# PULSE_TRIGGER.net
KiCad netlist of a schematic drawn in Altium Designer
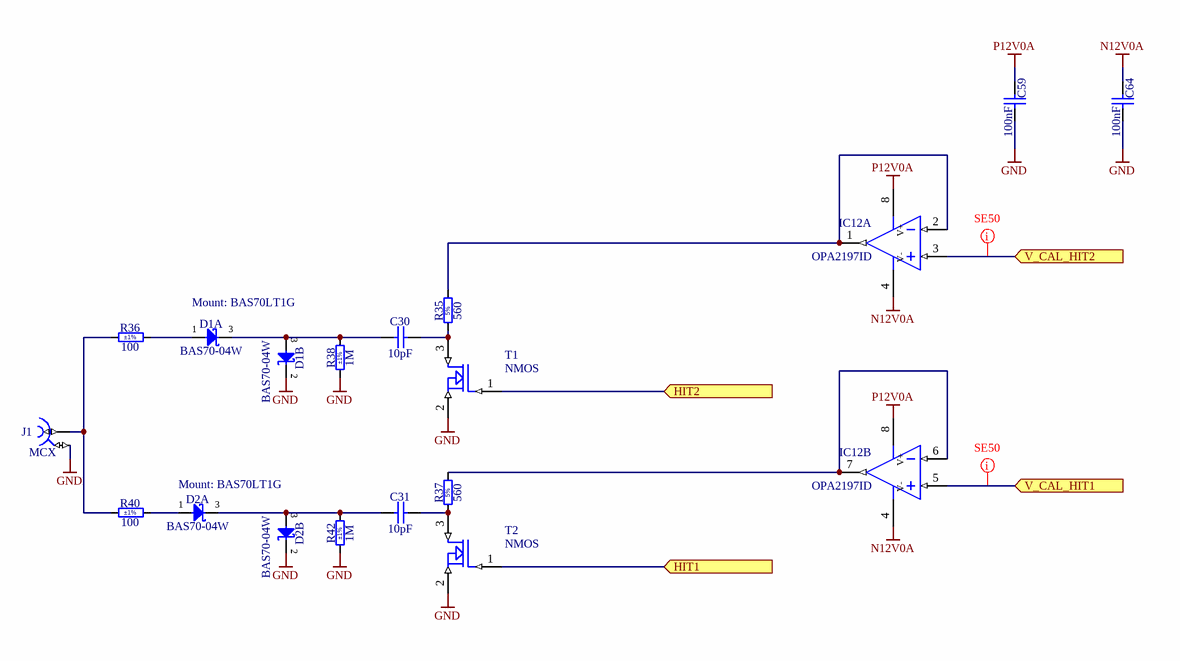
[diagram p0: PULSE_TRIGGER.SchDoc]

(export (version "E")
  (design (tool "Eeschema 10.0.6"))
  (components
    (comp (ref "C30")
      (value "10pF")
      (footprint "CAPC1608X87N")
      (description "Non-polarised capacitor")
      (fields
        (field (name "PART NUMBER") "CC0603_10PF_50V_5%_NP0")
        (field (name "VOLTAGE") "50V")
        (field (name "AUTHOR") "CERN DEM JLC")
      )
      (libsource (lib "Capacitors") (part "Capacitor - non polarized"))
    )
    (comp (ref "C31")
      (value "10pF")
      (footprint "CAPC1608X87N")
      (description "Non-polarised capacitor")
      (fields
        (field (name "PART NUMBER") "CC0603_10PF_50V_5%_NP0")
        (field (name "VOLTAGE") "50V")
        (field (name "AUTHOR") "CERN DEM JLC")
      )
      (libsource (lib "Capacitors") (part "Capacitor - non polarized"))
    )
    (comp (ref "C59")
      (value "100nF")
      (footprint "CAPC1005X55N")
      (description "Non-polarised capacitor")
      (fields
        (field (name "PART NUMBER") "CC0402_100NF_16V_10%_X7R")
        (field (name "VOLTAGE") "16V")
        (field (name "AUTHOR") "CERN DEM JLC")
      )
      (libsource (lib "Capacitors") (part "Capacitor - non polarized"))
    )
    (comp (ref "C64")
      (value "100nF")
      (footprint "CAPC1005X55N")
      (description "Non-polarised capacitor")
      (fields
        (field (name "PART NUMBER") "CC0402_100NF_16V_10%_X7R")
        (field (name "VOLTAGE") "16V")
        (field (name "AUTHOR") "CERN DEM JLC")
      )
      (libsource (lib "Capacitors") (part "Capacitor - non polarized"))
    )
    (comp (ref "D1")
      (value "BAS70-04W")
      (footprint "SOT65P210X110-3N")
      (description "Serial Schottky Diode")
      (fields
        (field (name "VOLTAGE") "70V")
        (field (name "POWER") "70mA")
        (field (name "AUTHOR") "CERN DEM JLC")
      )
      (libsource (lib "ICs And Semiconductors") (part "Diode Schottky x2 A1C3_A3C2"))
    )
    (comp (ref "D2")
      (value "BAS70-04W")
      (footprint "SOT65P210X110-3N")
      (description "Serial Schottky Diode")
      (fields
        (field (name "VOLTAGE") "70V")
        (field (name "POWER") "70mA")
        (field (name "AUTHOR") "CERN DEM JLC")
      )
      (libsource (lib "ICs And Semiconductors") (part "Diode Schottky x2 A1C3_A3C2"))
    )
    (comp (ref "IC12")
      (value "OPA2197ID")
      (footprint "SOIC127P600X175-8N")
      (description "Dual Operational Amplifier")
      (fields (field (name "MANUFACTURER") "TEXAS INSTRUMENTS") (field (name "AUTHOR") "CERN DEM MR"))
      (libsource (lib "ICs And Semiconductors") (part "Operational Amplifier x2 Type1"))
    )
    (comp (ref "J1")
      (value "MCX")
      (footprint "AMPHENOL_919-383J-51A")
      (fields
        (field (name "PART NUMBER") "AMPHENOL_919-383J-51A")
        (field (name "MANUFACTURER") "AMPHENOL")
        (field (name "MANUFACTURER PART NUMBER") "919-383J-51A")
        (field (name "AUTHOR") "CERN DEM BC")
      )
      (libsource (lib "Connectors") (part "Coax_1Female_1Shield"))
    )
    (comp (ref "R35")
      (value "560")
      (footprint "RESC2012X70N")
      (description "Resistor - 5%")
      (fields
        (field (name "PART NUMBER") "R0805_560R_5%_0.25W_200PPM_PANASONIC_ERJT")
        (field (name "POWER") "0.25W")
        (field (name "AUTHOR") "CERN DEM MR")
      )
      (libsource (lib "Resistors") (part "Resistor - 5%"))
    )
    (comp (ref "R36")
      (value "100")
      (footprint "RESC1608X55N")
      (description "Resistor - 1%")
      (fields
        (field (name "TOLERANCE") "±1%")
        (field (name "PART NUMBER") "R0603_100R_1%_0.1W_100PPM")
        (field (name "POWER") "0.1W")
        (field (name "AUTHOR") "CERN DEM JLC")
      )
      (libsource (lib "Resistors") (part "Resistor - 1%"))
    )
    (comp (ref "R37")
      (value "560")
      (footprint "RESC2012X70N")
      (description "Resistor - 5%")
      (fields
        (field (name "PART NUMBER") "R0805_560R_5%_0.25W_200PPM_PANASONIC_ERJT")
        (field (name "POWER") "0.25W")
        (field (name "AUTHOR") "CERN DEM MR")
      )
      (libsource (lib "Resistors") (part "Resistor - 5%"))
    )
    (comp (ref "R38")
      (value "1M")
      (footprint "RESC1608X55N")
      (description "Resistor - 1%")
      (fields
        (field (name "TOLERANCE") "±1%")
        (field (name "PART NUMBER") "R0603_1M_1%_0.1W_100PPM")
        (field (name "POWER") "0.1W")
        (field (name "AUTHOR") "CERN DEM JLC")
      )
      (libsource (lib "Resistors") (part "Resistor - 1%"))
    )
    (comp (ref "R40")
      (value "100")
      (footprint "RESC1608X55N")
      (description "Resistor - 1%")
      (fields
        (field (name "TOLERANCE") "±1%")
        (field (name "PART NUMBER") "R0603_100R_1%_0.1W_100PPM")
        (field (name "POWER") "0.1W")
        (field (name "AUTHOR") "CERN DEM JLC")
      )
      (libsource (lib "Resistors") (part "Resistor - 1%"))
    )
    (comp (ref "R42")
      (value "1M")
      (footprint "RESC1608X55N")
      (description "Resistor - 1%")
      (fields
        (field (name "TOLERANCE") "±1%")
        (field (name "PART NUMBER") "R0603_1M_1%_0.1W_100PPM")
        (field (name "POWER") "0.1W")
        (field (name "AUTHOR") "CERN DEM JLC")
      )
      (libsource (lib "Resistors") (part "Resistor - 1%"))
    )
    (comp (ref "T1")
      (value "NMOS")
      (footprint "CSD15380F3")
      (description "20-V, N channel NexFET™ power MOSFET, single LGA 0.6 mm x 0.7 mm, 1460 mOhm, gate ESD protection")
      (fields (field (name "MANUFACTURER PART NUMBER") "CSD15380F3"))
      (libsource (lib "LIBRARY_SCH") (part "Q_MOSFET N"))
    )
    (comp (ref "T2")
      (value "NMOS")
      (footprint "CSD15380F3")
      (description "20-V, N channel NexFET™ power MOSFET, single LGA 0.6 mm x 0.7 mm, 1460 mOhm, gate ESD protection")
      (fields (field (name "MANUFACTURER PART NUMBER") "CSD15380F3"))
      (libsource (lib "LIBRARY_SCH") (part "Q_MOSFET N"))
    )
  )
  (nets
    (net (code "1") (name "/HIT1") (class "Default")
      (node (ref "T2") (pin "1") (pinfunction "G_1") (pintype "input"))
    )
    (net (code "2") (name "/HIT2") (class "Default")
      (node (ref "T1") (pin "1") (pinfunction "G_1") (pintype "input"))
    )
    (net (code "3") (name "/V_CAL_HIT1") (class "Default")
      (node (ref "IC12") (pin "5") (pinfunction "IN+_5") (pintype "input"))
    )
    (net (code "4") (name "/V_CAL_HIT2") (class "Default")
      (node (ref "IC12") (pin "3") (pinfunction "IN+_3") (pintype "input"))
    )
    (net (code "5") (name "GND") (class "Default")
      (node (ref "C59") (pin "1") (pinfunction "1_1") (pintype "passive"))
      (node (ref "C64") (pin "1") (pinfunction "1_1") (pintype "passive"))
      (node (ref "D1") (pin "2") (pinfunction "C_2") (pintype "passive"))
      (node (ref "D2") (pin "2") (pinfunction "C_2") (pintype "passive"))
      (node (ref "J1") (pin "2") (pinfunction "2_2") (pintype "bidirectional"))
      (node (ref "R38") (pin "1") (pinfunction "1_1") (pintype "passive"))
      (node (ref "R42") (pin "1") (pinfunction "1_1") (pintype "passive"))
      (node (ref "T1") (pin "2") (pinfunction "S_2") (pintype "input"))
      (node (ref "T2") (pin "2") (pinfunction "S_2") (pintype "input"))
    )
    (net (code "6") (name "N12V0A") (class "Default")
      (node (ref "C64") (pin "2") (pinfunction "2_2") (pintype "passive"))
      (node (ref "IC12") (pin "4") (pinfunction "V-_4") (pintype "power_in"))
    )
    (net (code "7") (name "Net-(D1A-A)") (class "Default")
      (node (ref "D1") (pin "1") (pinfunction "A_1") (pintype "passive"))
      (node (ref "R36") (pin "2") (pinfunction "2_2") (pintype "passive"))
    )
    (net (code "8") (name "Net-(D1A-COMAC)") (class "Default")
      (node (ref "C30") (pin "1") (pinfunction "1_1") (pintype "passive"))
      (node (ref "D1") (pin "3") (pinfunction "COMAC_3") (pintype "passive"))
      (node (ref "R38") (pin "2") (pinfunction "2_2") (pintype "passive"))
    )
    (net (code "9") (name "Net-(D2A-A)") (class "Default")
      (node (ref "D2") (pin "1") (pinfunction "A_1") (pintype "passive"))
      (node (ref "R40") (pin "2") (pinfunction "2_2") (pintype "passive"))
    )
    (net (code "10") (name "Net-(D2A-COMAC)") (class "Default")
      (node (ref "C31") (pin "1") (pinfunction "1_1") (pintype "passive"))
      (node (ref "D2") (pin "3") (pinfunction "COMAC_3") (pintype "passive"))
      (node (ref "R42") (pin "2") (pinfunction "2_2") (pintype "passive"))
    )
    (net (code "11") (name "Net-(IC12A-IN-)") (class "Default")
      (node (ref "IC12") (pin "1") (pinfunction "OUT_1") (pintype "output"))
      (node (ref "IC12") (pin "2") (pinfunction "IN-_2") (pintype "input"))
      (node (ref "R35") (pin "2") (pinfunction "2_2") (pintype "passive"))
    )
    (net (code "12") (name "Net-(IC12B-IN-)") (class "Default")
      (node (ref "IC12") (pin "6") (pinfunction "IN-_6") (pintype "input"))
      (node (ref "IC12") (pin "7") (pinfunction "OUT_7") (pintype "output"))
      (node (ref "R37") (pin "2") (pinfunction "2_2") (pintype "passive"))
    )
    (net (code "13") (name "Net-(J1-Pad1)") (class "Default")
      (node (ref "J1") (pin "1") (pinfunction "1_1") (pintype "bidirectional"))
      (node (ref "R36") (pin "1") (pinfunction "1_1") (pintype "passive"))
      (node (ref "R40") (pin "1") (pinfunction "1_1") (pintype "passive"))
    )
    (net (code "14") (name "Net-(T1-D)") (class "Default")
      (node (ref "C30") (pin "2") (pinfunction "2_2") (pintype "passive"))
      (node (ref "R35") (pin "1") (pinfunction "1_1") (pintype "passive"))
      (node (ref "T1") (pin "3") (pinfunction "D_3") (pintype "input"))
    )
    (net (code "15") (name "Net-(T2-D)") (class "Default")
      (node (ref "C31") (pin "2") (pinfunction "2_2") (pintype "passive"))
      (node (ref "R37") (pin "1") (pinfunction "1_1") (pintype "passive"))
      (node (ref "T2") (pin "3") (pinfunction "D_3") (pintype "input"))
    )
    (net (code "16") (name "P12V0A") (class "Default")
      (node (ref "C59") (pin "2") (pinfunction "2_2") (pintype "passive"))
      (node (ref "IC12") (pin "8") (pinfunction "V+_8") (pintype "power_in"))
    )
  )
)
